# base.net
KiCad netlist of a schematic drawn in EAGLE
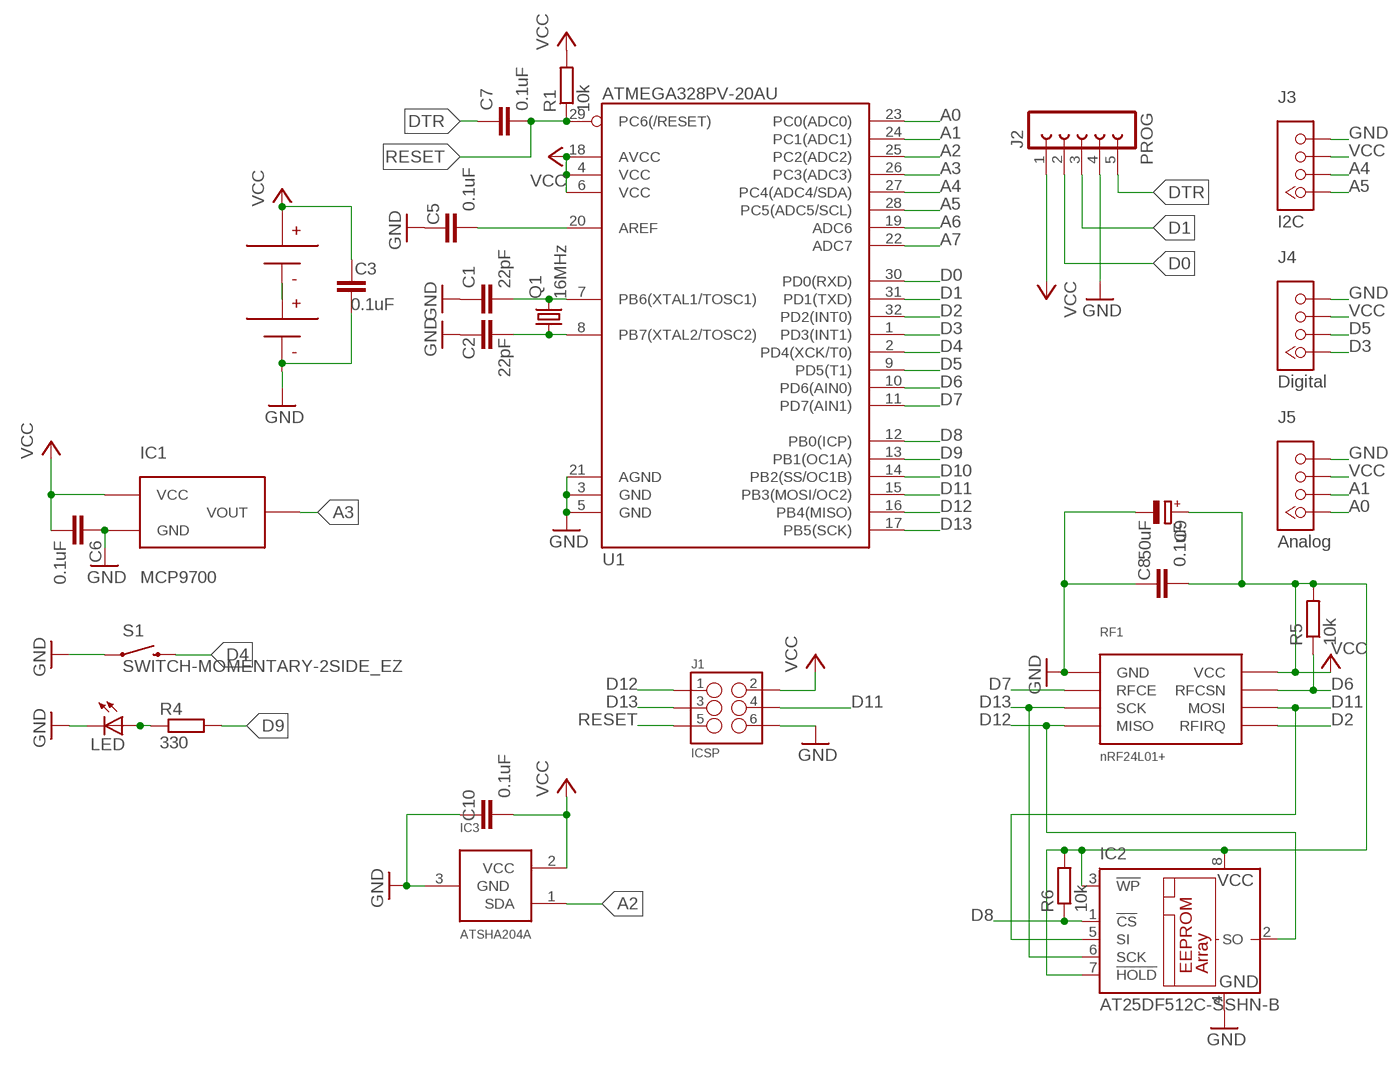
[diagram p0: schematic, sheet 1]

(export (version "E")
  (design (tool "Eeschema 10.0.6"))
  (components
    (comp (ref "BATT1")
      (value "AAA-HOLDER")
      (footprint "eagle-import:AAA-HOLDER")
      (libsource (lib "eagle-import") (part "AAA-HOLDER"))
    )
    (comp (ref "BATT2")
      (value "AAA-HOLDER")
      (footprint "eagle-import:AAA-HOLDER")
      (libsource (lib "eagle-import") (part "AAA-HOLDER"))
    )
    (comp (ref "C1")
      (value "22pF")
      (footprint "eagle-import:C0805")
      (libsource (lib "eagle-import") (part "C-EUC0805"))
    )
    (comp (ref "C2")
      (value "22pF")
      (footprint "eagle-import:C0805")
      (libsource (lib "eagle-import") (part "C-EUC0805"))
    )
    (comp (ref "C3")
      (value "0.1uF")
      (footprint "eagle-import:C0805")
      (libsource (lib "eagle-import") (part "C-EUC0805"))
    )
    (comp (ref "C5")
      (value "0.1uF")
      (footprint "eagle-import:C0805")
      (libsource (lib "eagle-import") (part "C-EUC0805"))
    )
    (comp (ref "C6")
      (value "0.1uF")
      (footprint "eagle-import:C0805")
      (libsource (lib "eagle-import") (part "C-EUC0805"))
    )
    (comp (ref "C7")
      (value "0.1uF")
      (footprint "eagle-import:C0805")
      (libsource (lib "eagle-import") (part "C-EUC0805"))
    )
    (comp (ref "C8")
      (value "0.1uF")
      (footprint "eagle-import:C0805")
      (libsource (lib "eagle-import") (part "C-EUC0805"))
    )
    (comp (ref "C9")
      (value "50uF")
      (footprint "eagle-import:SMC_C")
      (libsource (lib "eagle-import") (part "CPOL-EUSMCC"))
    )
    (comp (ref "C10")
      (value "0.1uF")
      (footprint "eagle-import:C0805")
      (libsource (lib "eagle-import") (part "C-EUC0805"))
    )
    (comp (ref "IC1")
      (value "MCP9700")
      (footprint "eagle-import:SOT23")
      (libsource (lib "eagle-import") (part "MCP9700"))
    )
    (comp (ref "IC2")
      (value "AT25DF512C-SSHN-B")
      (footprint "eagle-import:SO-08")
      (fields (field (name "MF") "MICROCHIP") (field (name "MPN") "25AA080/SN"))
      (libsource (lib "eagle-import") (part "25SNAA080"))
    )
    (comp (ref "IC3")
      (value "ATSHA204A")
      (footprint "eagle-import:SOT23")
      (libsource (lib "eagle-import") (part "ATSHA204A"))
    )
    (comp (ref "J1")
      (value "ICSP")
      (footprint "eagle-import:2X3-NS")
      (libsource (lib "eagle-import") (part "M03X2NO_SILK"))
    )
    (comp (ref "J3")
      (value "I2C")
      (footprint "eagle-import:TWIG-4P-2.0")
      (libsource (lib "eagle-import") (part "TWIG-4P-2.0"))
    )
    (comp (ref "J4")
      (value "Digital")
      (footprint "eagle-import:TWIG-4P-2.0")
      (libsource (lib "eagle-import") (part "TWIG-4P-2.0"))
    )
    (comp (ref "J5")
      (value "Analog")
      (footprint "eagle-import:TWIG-4P-2.0")
      (libsource (lib "eagle-import") (part "TWIG-4P-2.0"))
    )
    (comp (ref "LED")
      (value "LEDCHIPLED_0805")
      (footprint "eagle-import:CHIPLED_0805")
      (libsource (lib "eagle-import") (part "LEDCHIPLED_0805"))
    )
    (comp (ref "PROG")
      (value "J2")
      (footprint "eagle-import:FE05-1")
      (libsource (lib "eagle-import") (part "FE05-1"))
    )
    (comp (ref "Q1")
      (value "16MHz")
      (footprint "eagle-import:CTS406")
      (libsource (lib "eagle-import") (part "CRYSTALCTS406"))
    )
    (comp (ref "R1")
      (value "10k")
      (footprint "eagle-import:R0805")
      (libsource (lib "eagle-import") (part "R-EU_R0805"))
    )
    (comp (ref "R4")
      (value "330")
      (footprint "eagle-import:R0805")
      (libsource (lib "eagle-import") (part "R-EU_R0805"))
    )
    (comp (ref "R5")
      (value "10k")
      (footprint "eagle-import:R0805")
      (libsource (lib "eagle-import") (part "R-EU_R0805"))
    )
    (comp (ref "R6")
      (value "10k")
      (footprint "eagle-import:R0805")
      (libsource (lib "eagle-import") (part "R-EU_R0805"))
    )
    (comp (ref "RF1")
      (value "nRF24L01+")
      (footprint "eagle-import:2X4-2.54MM")
      (libsource (lib "eagle-import") (part "NRF24L01"))
    )
    (comp (ref "S1")
      (value "SWITCH-MOMENTARY-2SIDE_EZ")
      (footprint "eagle-import:TACTILE-PTH-SIDEEZ")
      (libsource (lib "eagle-import") (part "SWITCH-MOMENTARY-2SIDE_EZ"))
    )
    (comp (ref "U1")
      (value "ATMEGA328PV-20AU")
      (footprint "eagle-import:TQFP32-08")
      (libsource (lib "eagle-import") (part "ATMEGA328_SMT"))
    )
  )
  (nets
    (net (code "1") (name "/A0") (class "Default")
      (node (ref "J5") (pin "P$1") (pinfunction "P$1_P$1") (pintype "bidirectional"))
      (node (ref "U1") (pin "23") (pinfunction "PC0(ADC0)_23") (pintype "bidirectional"))
    )
    (net (code "2") (name "/A1") (class "Default")
      (node (ref "J5") (pin "P$2") (pinfunction "P$2_P$2") (pintype "bidirectional"))
      (node (ref "U1") (pin "24") (pinfunction "PC1(ADC1)_24") (pintype "bidirectional"))
    )
    (net (code "3") (name "/A4") (class "Default")
      (node (ref "J3") (pin "P$2") (pinfunction "P$2_P$2") (pintype "bidirectional"))
      (node (ref "U1") (pin "27") (pinfunction "PC4(ADC4/SDA)_27") (pintype "bidirectional"))
    )
    (net (code "4") (name "/A5") (class "Default")
      (node (ref "J3") (pin "P$1") (pinfunction "P$1_P$1") (pintype "bidirectional"))
      (node (ref "U1") (pin "28") (pinfunction "PC5(ADC5/SCL)_28") (pintype "bidirectional"))
    )
    (net (code "5") (name "/A6") (class "Default")
      (node (ref "U1") (pin "19") (pinfunction "ADC6_19") (pintype "bidirectional"))
    )
    (net (code "6") (name "/A7") (class "Default")
      (node (ref "U1") (pin "22") (pinfunction "ADC7_22") (pintype "bidirectional"))
    )
    (net (code "7") (name "/D2") (class "Default")
      (node (ref "RF1") (pin "P$8") (pinfunction "RFIRQ_P$8") (pintype "output"))
      (node (ref "U1") (pin "32") (pinfunction "PD2(INT0)_32") (pintype "bidirectional"))
    )
    (net (code "8") (name "/D3") (class "Default")
      (node (ref "J4") (pin "P$1") (pinfunction "P$1_P$1") (pintype "bidirectional"))
      (node (ref "U1") (pin "1") (pinfunction "PD3(INT1)_1") (pintype "bidirectional"))
    )
    (net (code "9") (name "/D5") (class "Default")
      (node (ref "J4") (pin "P$2") (pinfunction "P$2_P$2") (pintype "bidirectional"))
      (node (ref "U1") (pin "9") (pinfunction "PD5(T1)_9") (pintype "bidirectional"))
    )
    (net (code "10") (name "/D6") (class "Default")
      (node (ref "R5") (pin "1") (pinfunction "1_1") (pintype "passive"))
      (node (ref "RF1") (pin "P$4") (pinfunction "RFCSN_P$4") (pintype "bidirectional"))
      (node (ref "U1") (pin "10") (pinfunction "PD6(AIN0)_10") (pintype "bidirectional"))
    )
    (net (code "11") (name "/D7") (class "Default")
      (node (ref "RF1") (pin "P$3") (pinfunction "RFCE_P$3") (pintype "input"))
      (node (ref "U1") (pin "11") (pinfunction "PD7(AIN1)_11") (pintype "bidirectional"))
    )
    (net (code "12") (name "/D8") (class "Default")
      (node (ref "IC2") (pin "1") (pinfunction "~{CS}_1") (pintype "input"))
      (node (ref "R6") (pin "1") (pinfunction "1_1") (pintype "passive"))
      (node (ref "U1") (pin "12") (pinfunction "PB0(ICP)_12") (pintype "bidirectional"))
    )
    (net (code "13") (name "/D10") (class "Default")
      (node (ref "U1") (pin "14") (pinfunction "PB2(SS/OC1B)_14") (pintype "bidirectional"))
    )
    (net (code "14") (name "/D11") (class "Default")
      (node (ref "IC2") (pin "5") (pinfunction "SI_5") (pintype "input"))
      (node (ref "J1") (pin "4") (pinfunction "4_4") (pintype "bidirectional"))
      (node (ref "RF1") (pin "P$6") (pinfunction "MOSI_P$6") (pintype "bidirectional"))
      (node (ref "U1") (pin "15") (pinfunction "PB3(MOSI/OC2)_15") (pintype "bidirectional"))
    )
    (net (code "15") (name "/D12") (class "Default")
      (node (ref "IC2") (pin "2") (pinfunction "SO_2") (pintype "bidirectional"))
      (node (ref "J1") (pin "1") (pinfunction "1_1") (pintype "bidirectional"))
      (node (ref "RF1") (pin "P$7") (pinfunction "MISO_P$7") (pintype "bidirectional"))
      (node (ref "U1") (pin "16") (pinfunction "PB4(MISO)_16") (pintype "bidirectional"))
    )
    (net (code "16") (name "/D13") (class "Default")
      (node (ref "IC2") (pin "6") (pinfunction "SCK_6") (pintype "input"))
      (node (ref "J1") (pin "3") (pinfunction "3_3") (pintype "bidirectional"))
      (node (ref "RF1") (pin "P$5") (pinfunction "SCK_P$5") (pintype "input"))
      (node (ref "U1") (pin "17") (pinfunction "PB5(SCK)_17") (pintype "bidirectional"))
    )
    (net (code "17") (name "A2") (class "Default")
      (node (ref "IC3") (pin "1") (pinfunction "SDA_1") (pintype "bidirectional"))
      (node (ref "U1") (pin "25") (pinfunction "PC2(ADC2)_25") (pintype "bidirectional"))
    )
    (net (code "18") (name "A3") (class "Default")
      (node (ref "IC1") (pin "VOUT") (pinfunction "VOUT_VOUT") (pintype "output"))
      (node (ref "U1") (pin "26") (pinfunction "PC3(ADC3)_26") (pintype "bidirectional"))
    )
    (net (code "19") (name "D0") (class "Default")
      (node (ref "PROG") (pin "2") (pinfunction "2_2") (pintype "passive"))
      (node (ref "U1") (pin "30") (pinfunction "PD0(RXD)_30") (pintype "bidirectional"))
    )
    (net (code "20") (name "D1") (class "Default")
      (node (ref "PROG") (pin "3") (pinfunction "3_3") (pintype "passive"))
      (node (ref "U1") (pin "31") (pinfunction "PD1(TXD)_31") (pintype "bidirectional"))
    )
    (net (code "21") (name "D4") (class "Default")
      (node (ref "S1") (pin "2") (pinfunction "2_2") (pintype "passive"))
      (node (ref "U1") (pin "2") (pinfunction "PD4(XCK/T0)_2") (pintype "bidirectional"))
    )
    (net (code "22") (name "D9") (class "Default")
      (node (ref "R4") (pin "2") (pinfunction "2_2") (pintype "passive"))
      (node (ref "U1") (pin "13") (pinfunction "PB1(OC1A)_13") (pintype "bidirectional"))
    )
    (net (code "23") (name "DTR") (class "Default")
      (node (ref "C7") (pin "1") (pinfunction "1_1") (pintype "passive"))
      (node (ref "PROG") (pin "5") (pinfunction "5_5") (pintype "passive"))
    )
    (net (code "24") (name "GND") (class "Default")
      (node (ref "BATT2") (pin "MINUS") (pinfunction "MINUS_MINUS") (pintype "power_in"))
      (node (ref "C1") (pin "1") (pinfunction "1_1") (pintype "passive"))
      (node (ref "C10") (pin "2") (pinfunction "2_2") (pintype "passive"))
      (node (ref "C2") (pin "1") (pinfunction "1_1") (pintype "passive"))
      (node (ref "C3") (pin "1") (pinfunction "1_1") (pintype "passive"))
      (node (ref "C5") (pin "2") (pinfunction "2_2") (pintype "passive"))
      (node (ref "C6") (pin "1") (pinfunction "1_1") (pintype "passive"))
      (node (ref "C8") (pin "2") (pinfunction "2_2") (pintype "passive"))
      (node (ref "C9") (pin "-") (pinfunction "-_-") (pintype "passive"))
      (node (ref "IC1") (pin "GND") (pinfunction "GND_GND") (pintype "power_in"))
      (node (ref "IC2") (pin "4") (pinfunction "GND_4") (pintype "power_in"))
      (node (ref "IC3") (pin "3") (pinfunction "GND_3") (pintype "bidirectional"))
      (node (ref "J1") (pin "6") (pinfunction "6_6") (pintype "bidirectional"))
      (node (ref "J3") (pin "P$4") (pinfunction "P$4_P$4") (pintype "bidirectional"))
      (node (ref "J4") (pin "P$4") (pinfunction "P$4_P$4") (pintype "bidirectional"))
      (node (ref "J5") (pin "P$4") (pinfunction "P$4_P$4") (pintype "bidirectional"))
      (node (ref "LED") (pin "C") (pinfunction "C_C") (pintype "passive"))
      (node (ref "PROG") (pin "4") (pinfunction "4_4") (pintype "passive"))
      (node (ref "RF1") (pin "P$1") (pinfunction "GND_P$1") (pintype "power_in"))
      (node (ref "S1") (pin "1") (pinfunction "1_1") (pintype "passive"))
      (node (ref "U1") (pin "21") (pinfunction "AGND_21") (pintype "bidirectional"))
      (node (ref "U1") (pin "3") (pinfunction "GND_3") (pintype "bidirectional"))
      (node (ref "U1") (pin "5") (pinfunction "GND_5") (pintype "bidirectional"))
    )
    (net (code "25") (name "Net-(BATT1-PadMINUS)") (class "Default")
      (node (ref "BATT1") (pin "MINUS") (pinfunction "MINUS_MINUS") (pintype "power_in"))
      (node (ref "BATT2") (pin "PLUS") (pinfunction "PLUS_PLUS") (pintype "power_in"))
    )
    (net (code "26") (name "Net-(LED-PadA)") (class "Default")
      (node (ref "LED") (pin "A") (pinfunction "A_A") (pintype "passive"))
      (node (ref "R4") (pin "1") (pinfunction "1_1") (pintype "passive"))
    )
    (net (code "27") (name "Net-(Q1-2)") (class "Default")
      (node (ref "C1") (pin "2") (pinfunction "2_2") (pintype "passive"))
      (node (ref "Q1") (pin "3") (pinfunction "2_3") (pintype "passive"))
      (node (ref "U1") (pin "7") (pinfunction "PB6(XTAL1/TOSC1)_7") (pintype "bidirectional"))
    )
    (net (code "28") (name "Net-(U1-AREF)") (class "Default")
      (node (ref "C5") (pin "1") (pinfunction "1_1") (pintype "passive"))
      (node (ref "U1") (pin "20") (pinfunction "AREF_20") (pintype "bidirectional"))
    )
    (net (code "29") (name "Net-(U1-PB7(XTAL2{slash}TOSC2))") (class "Default")
      (node (ref "C2") (pin "2") (pinfunction "2_2") (pintype "passive"))
      (node (ref "Q1") (pin "1") (pinfunction "1_1") (pintype "passive"))
      (node (ref "U1") (pin "8") (pinfunction "PB7(XTAL2/TOSC2)_8") (pintype "bidirectional"))
    )
    (net (code "30") (name "RESET") (class "Default")
      (node (ref "C7") (pin "2") (pinfunction "2_2") (pintype "passive"))
      (node (ref "J1") (pin "5") (pinfunction "5_5") (pintype "bidirectional"))
      (node (ref "R1") (pin "1") (pinfunction "1_1") (pintype "passive"))
      (node (ref "U1") (pin "29") (pinfunction "PC6(/RESET)_29") (pintype "bidirectional"))
    )
    (net (code "31") (name "VCC") (class "Default")
      (node (ref "BATT1") (pin "PLUS") (pinfunction "PLUS_PLUS") (pintype "power_in"))
      (node (ref "C10") (pin "1") (pinfunction "1_1") (pintype "passive"))
      (node (ref "C3") (pin "2") (pinfunction "2_2") (pintype "passive"))
      (node (ref "C6") (pin "2") (pinfunction "2_2") (pintype "passive"))
      (node (ref "C8") (pin "1") (pinfunction "1_1") (pintype "passive"))
      (node (ref "C9") (pin "+") (pinfunction "+_+") (pintype "passive"))
      (node (ref "IC1") (pin "VDD") (pinfunction "VCC_VDD") (pintype "power_in"))
      (node (ref "IC2") (pin "3") (pinfunction "~{WP}_3") (pintype "input"))
      (node (ref "IC2") (pin "7") (pinfunction "~{HOLD}_7") (pintype "input"))
      (node (ref "IC2") (pin "8") (pinfunction "VCC_8") (pintype "power_in"))
      (node (ref "IC3") (pin "2") (pinfunction "VCC_2") (pintype "bidirectional"))
      (node (ref "J1") (pin "2") (pinfunction "2_2") (pintype "bidirectional"))
      (node (ref "J3") (pin "P$3") (pinfunction "P$3_P$3") (pintype "bidirectional"))
      (node (ref "J4") (pin "P$3") (pinfunction "P$3_P$3") (pintype "bidirectional"))
      (node (ref "J5") (pin "P$3") (pinfunction "P$3_P$3") (pintype "bidirectional"))
      (node (ref "PROG") (pin "1") (pinfunction "1_1") (pintype "passive"))
      (node (ref "R1") (pin "2") (pinfunction "2_2") (pintype "passive"))
      (node (ref "R5") (pin "2") (pinfunction "2_2") (pintype "passive"))
      (node (ref "R6") (pin "2") (pinfunction "2_2") (pintype "passive"))
      (node (ref "RF1") (pin "P$2") (pinfunction "VCC_P$2") (pintype "power_in"))
      (node (ref "U1") (pin "18") (pinfunction "AVCC_18") (pintype "bidirectional"))
      (node (ref "U1") (pin "4") (pinfunction "VCC_4") (pintype "bidirectional"))
      (node (ref "U1") (pin "6") (pinfunction "VCC_6") (pintype "bidirectional"))
    )
  )
)
